# Ports.net
KiCad netlist of a schematic drawn in Altium Designer
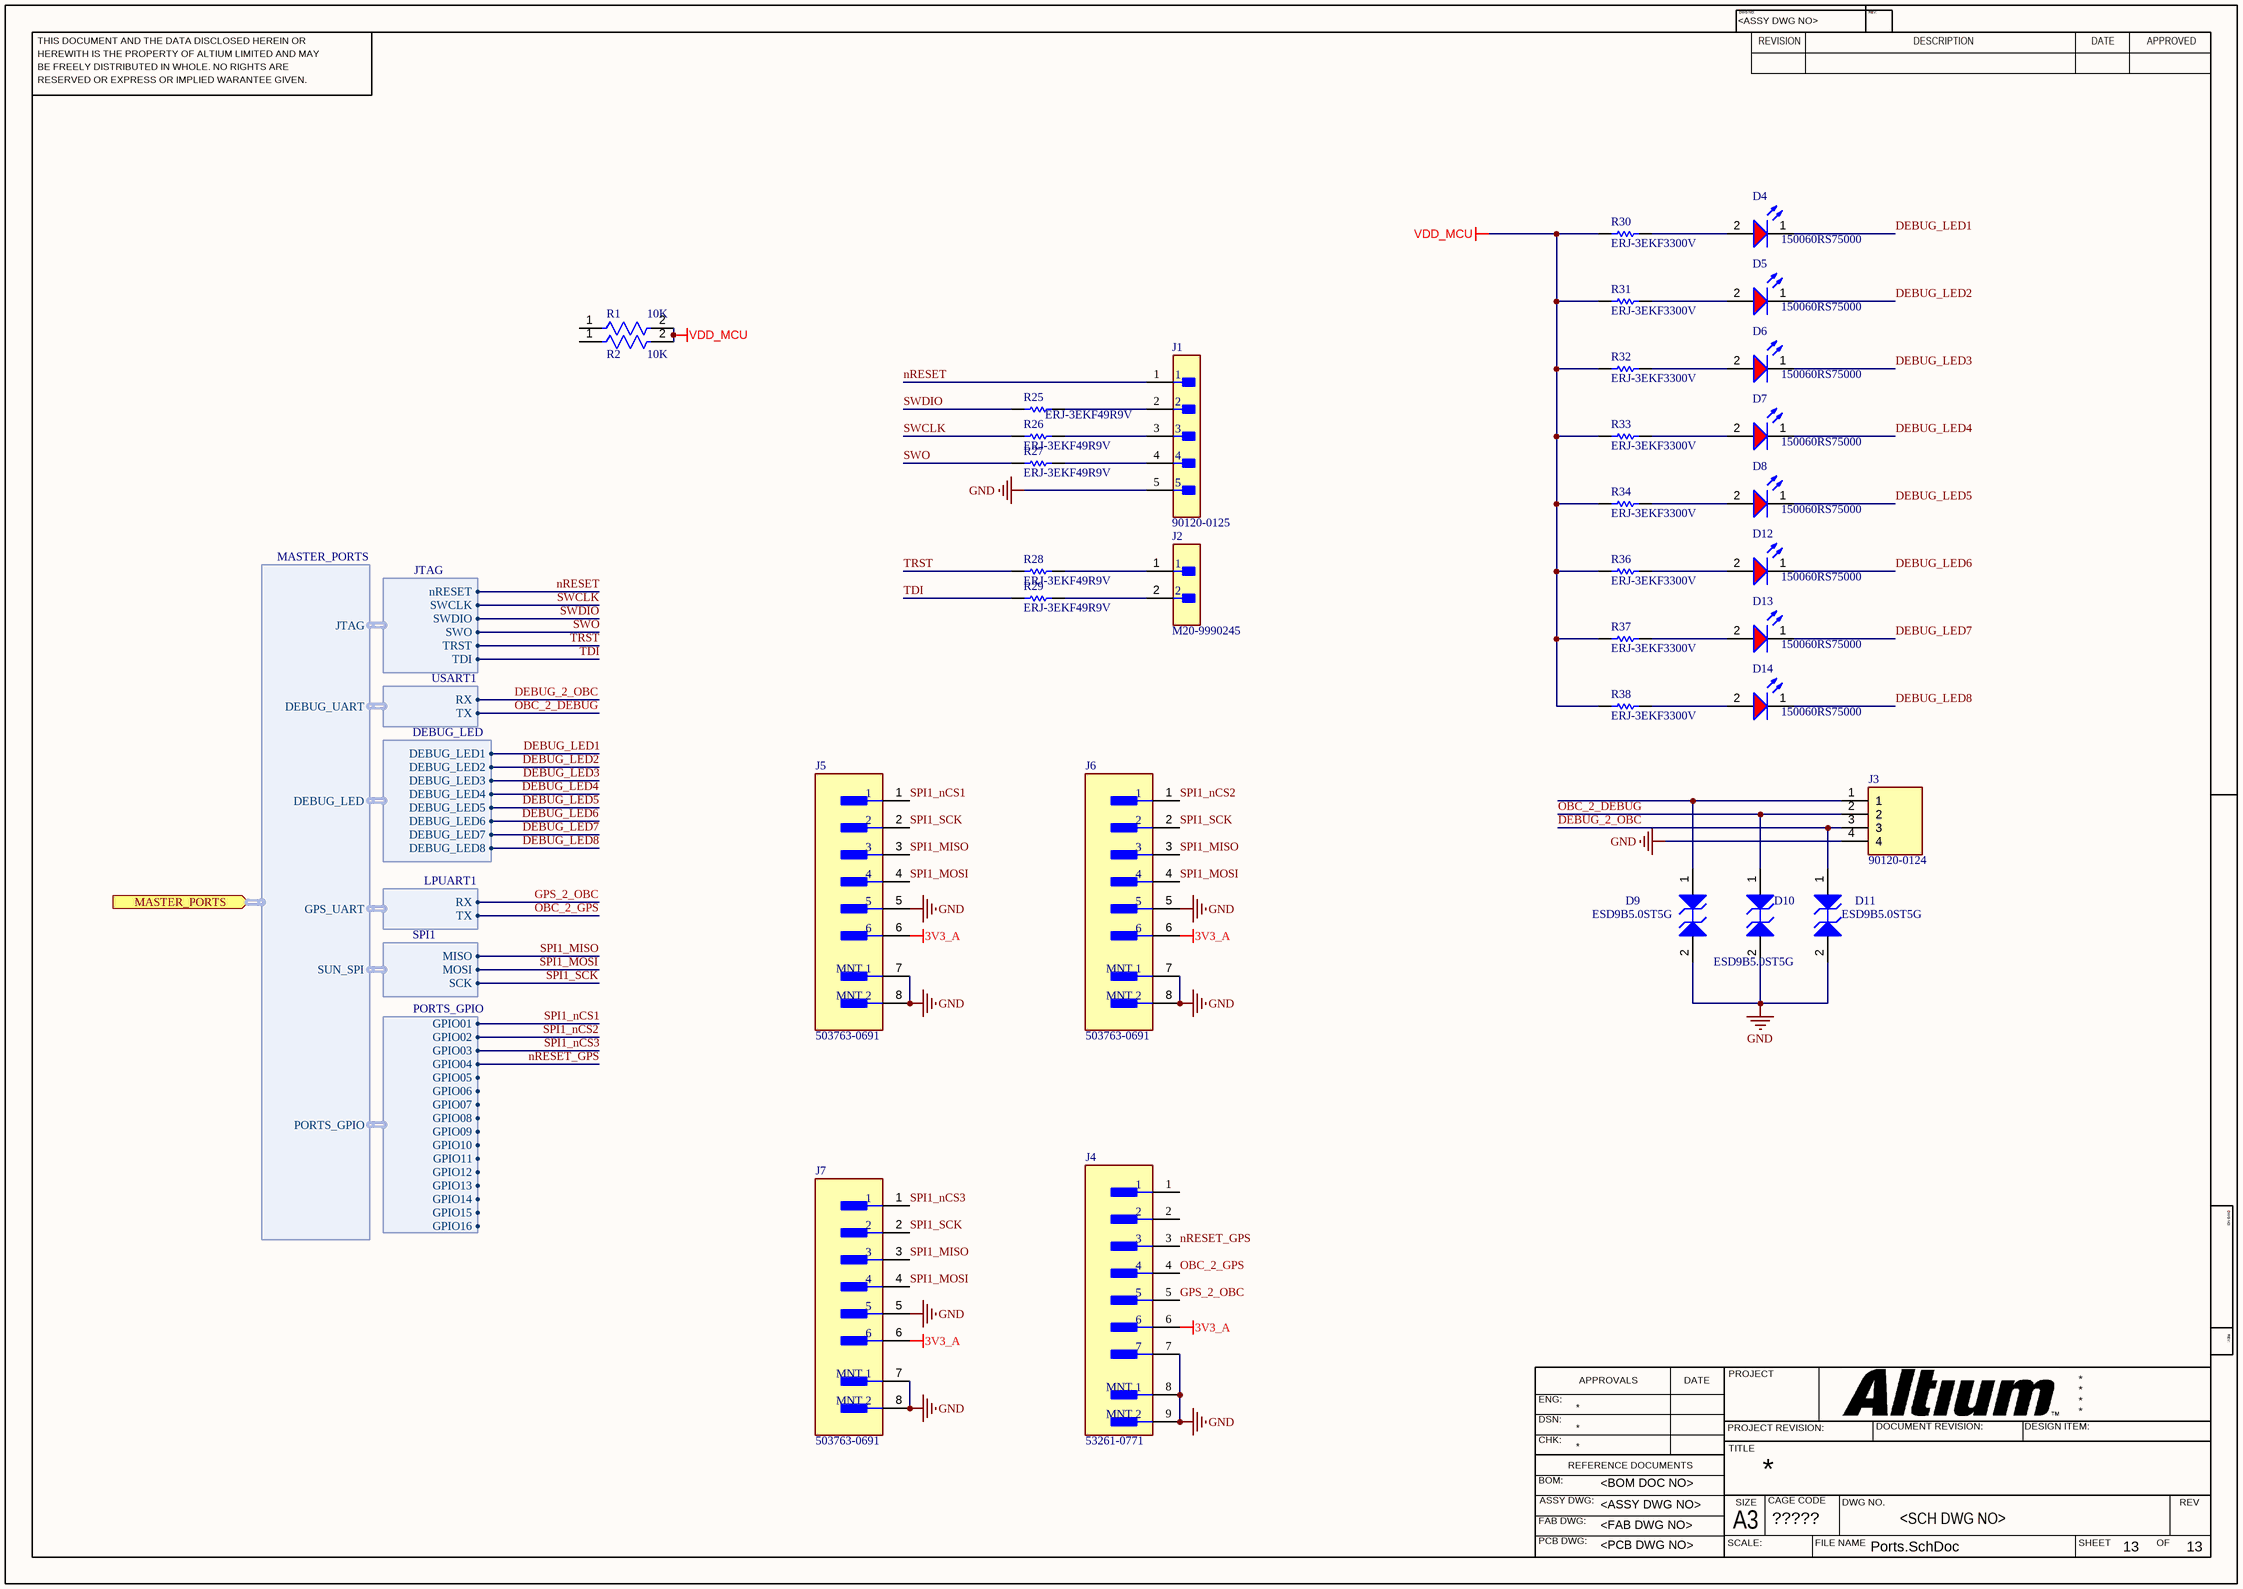
[diagram p0: Ports.SchDoc]

(export (version "E")
  (design (tool "Eeschema 10.0.6"))
  (components
    (comp (ref "D4")
      (value "150060RS75000")
      (footprint "WL-SMCW_0603_150060xx75000")
      (description "LED Low-Power Uni-Color Red 630nm 2V 2-Pin Chip 0603(1608Metric) T/R")
      (libsource (lib "Altium Content Vault") (part "LED_Red_2A-1K"))
    )
    (comp (ref "D5")
      (value "150060RS75000")
      (footprint "WL-SMCW_0603_150060xx75000")
      (description "LED Low-Power Uni-Color Red 630nm 2V 2-Pin Chip 0603(1608Metric) T/R")
      (libsource (lib "Altium Content Vault") (part "LED_Red_2A-1K"))
    )
    (comp (ref "D6")
      (value "150060RS75000")
      (footprint "WL-SMCW_0603_150060xx75000")
      (description "LED Low-Power Uni-Color Red 630nm 2V 2-Pin Chip 0603(1608Metric) T/R")
      (libsource (lib "Altium Content Vault") (part "LED_Red_2A-1K"))
    )
    (comp (ref "D7")
      (value "150060RS75000")
      (footprint "WL-SMCW_0603_150060xx75000")
      (description "LED Low-Power Uni-Color Red 630nm 2V 2-Pin Chip 0603(1608Metric) T/R")
      (libsource (lib "Altium Content Vault") (part "LED_Red_2A-1K"))
    )
    (comp (ref "D8")
      (value "150060RS75000")
      (footprint "WL-SMCW_0603_150060xx75000")
      (description "LED Low-Power Uni-Color Red 630nm 2V 2-Pin Chip 0603(1608Metric) T/R")
      (libsource (lib "Altium Content Vault") (part "LED_Red_2A-1K"))
    )
    (comp (ref "D9")
      (value "ESD9B5.0ST5G")
      (footprint "ONSC-SOD-923-2-514AB-01_V")
      (fields (field (name "MANUFACTURER") "On Semiconductor"))
      (libsource (lib "Altium Content Vault") (part "ONSC-A1A2-2"))
    )
    (comp (ref "D10")
      (value "ESD9B5.0ST5G")
      (footprint "ONSC-SOD-923-2-514AB-01_V")
      (fields (field (name "MANUFACTURER") "On Semiconductor"))
      (libsource (lib "Altium Content Vault") (part "ONSC-A1A2-2"))
    )
    (comp (ref "D11")
      (value "ESD9B5.0ST5G")
      (footprint "ONSC-SOD-923-2-514AB-01_V")
      (fields (field (name "MANUFACTURER") "On Semiconductor"))
      (libsource (lib "Altium Content Vault") (part "ONSC-A1A2-2"))
    )
    (comp (ref "D12")
      (value "150060RS75000")
      (footprint "WL-SMCW_0603_150060xx75000")
      (description "LED Low-Power Uni-Color Red 630nm 2V 2-Pin Chip 0603(1608Metric) T/R")
      (libsource (lib "Altium Content Vault") (part "LED_Red_2A-1K"))
    )
    (comp (ref "D13")
      (value "150060RS75000")
      (footprint "WL-SMCW_0603_150060xx75000")
      (description "LED Low-Power Uni-Color Red 630nm 2V 2-Pin Chip 0603(1608Metric) T/R")
      (libsource (lib "Altium Content Vault") (part "LED_Red_2A-1K"))
    )
    (comp (ref "D14")
      (value "150060RS75000")
      (footprint "WL-SMCW_0603_150060xx75000")
      (description "LED Low-Power Uni-Color Red 630nm 2V 2-Pin Chip 0603(1608Metric) T/R")
      (libsource (lib "Altium Content Vault") (part "LED_Red_2A-1K"))
    )
    (comp (ref "J1")
      (value "90120-0125")
      (footprint "FP-90120-0125-MFG")
      (description "90120-0125 2.54mm Pitch C-Grid III Header, Single Row, Vertical, 5 Circuits, Tin (Sn) Plating")
      (libsource (lib "Altium Content Vault") (part "bf93c07fd2649a848d0ec8585582aab"))
    )
    (comp (ref "J2")
      (value "M20-9990245")
      (footprint "FP-M20-9990245-MFG")
      (description "CONN HEADER VERT 2POS 2.54MM")
      (fields (field (name "VOLTAGE") "50V"))
      (libsource (lib "Altium Content Vault") (part "3bc925449376181038e59eaffc5286c"))
    )
    (comp (ref "J3")
      (value "90120-0124")
      (footprint "SamacSys:HDRV4W65P0X254_1X4_1016X254X945P")
      (description "Connector")
      (fields (field (name "MOUSER PART NUMBER") "538-90120-0124"))
      (libsource (lib "*") (part "90120-0124"))
    )
    (comp (ref "J4")
      (value "53261-0771")
      (footprint "FP-53261-0771-MFG")
      (description "CONN HEADER SMD R/A 7POS 1.25MM")
      (libsource (lib "Altium Content Vault") (part "bf8db8d8d9f0c3af2da8de9d3b974a9"))
    )
    (comp (ref "J5")
      (value "503763-0691")
      (footprint "FP-503763-0691-MFG")
      (description "CONN HEADER SMD R/A 6POS 1MM")
      (libsource (lib "Altium Content Vault") (part "ed24c53d9ba001d1a2a686240a95171"))
    )
    (comp (ref "J6")
      (value "503763-0691")
      (footprint "FP-503763-0691-MFG")
      (description "CONN HEADER SMD R/A 6POS 1MM")
      (libsource (lib "Altium Content Vault") (part "ed24c53d9ba001d1a2a686240a95171"))
    )
    (comp (ref "J7")
      (value "503763-0691")
      (footprint "FP-503763-0691-MFG")
      (description "CONN HEADER SMD R/A 6POS 1MM")
      (libsource (lib "Altium Content Vault") (part "ed24c53d9ba001d1a2a686240a95171"))
    )
    (comp (ref "R1")
      (value "10K")
      (footprint "FP-RK73B1J-MFG")
      (description "RES 10K OHM 5% 1/10W 0603")
      (fields (field (name "TOLERANCE") "5%"))
      (libsource (lib "Altium Content Vault") (part "1029c3af85768c4190bb7ad29bc67b5"))
    )
    (comp (ref "R2")
      (value "10K")
      (footprint "FP-RK73B1J-MFG")
      (description "RES 10K OHM 5% 1/10W 0603")
      (fields (field (name "TOLERANCE") "5%"))
      (libsource (lib "Altium Content Vault") (part "1029c3af85768c4190bb7ad29bc67b5"))
    )
    (comp (ref "R25")
      (value "ERJ-3EKF49R9V")
      (footprint "RESC1608X55X30ML15T15")
      (fields (field (name "MANUFACTURER") "Panasonic"))
      (libsource (lib "Altium Content Vault") (part "RES"))
    )
    (comp (ref "R26")
      (value "ERJ-3EKF49R9V")
      (footprint "RESC1608X55X30ML15T15")
      (fields (field (name "MANUFACTURER") "Panasonic"))
      (libsource (lib "Altium Content Vault") (part "RES"))
    )
    (comp (ref "R27")
      (value "ERJ-3EKF49R9V")
      (footprint "RESC1608X55X30ML15T15")
      (fields (field (name "MANUFACTURER") "Panasonic"))
      (libsource (lib "Altium Content Vault") (part "RES"))
    )
    (comp (ref "R28")
      (value "ERJ-3EKF49R9V")
      (footprint "RESC1608X55X30ML15T15")
      (fields (field (name "MANUFACTURER") "Panasonic"))
      (libsource (lib "Altium Content Vault") (part "RES"))
    )
    (comp (ref "R29")
      (value "ERJ-3EKF49R9V")
      (footprint "RESC1608X55X30ML15T15")
      (fields (field (name "MANUFACTURER") "Panasonic"))
      (libsource (lib "Altium Content Vault") (part "RES"))
    )
    (comp (ref "R30")
      (value "ERJ-3EKF3300V")
      (footprint "RESC1608X55X30LL15T15")
      (description "Chip Resistor, 330 Ohm, +/- 1%, 0.1 W, -55 to 155 degC, 0603 (1608 Metric), RoHS, Tape and Reel")
      (libsource (lib "Altium Content Vault") (part "RES-2"))
    )
    (comp (ref "R31")
      (value "ERJ-3EKF3300V")
      (footprint "RESC1608X55X30LL15T15")
      (description "Chip Resistor, 330 Ohm, +/- 1%, 0.1 W, -55 to 155 degC, 0603 (1608 Metric), RoHS, Tape and Reel")
      (libsource (lib "Altium Content Vault") (part "RES-2"))
    )
    (comp (ref "R32")
      (value "ERJ-3EKF3300V")
      (footprint "RESC1608X55X30LL15T15")
      (description "Chip Resistor, 330 Ohm, +/- 1%, 0.1 W, -55 to 155 degC, 0603 (1608 Metric), RoHS, Tape and Reel")
      (libsource (lib "Altium Content Vault") (part "RES-2"))
    )
    (comp (ref "R33")
      (value "ERJ-3EKF3300V")
      (footprint "RESC1608X55X30LL15T15")
      (description "Chip Resistor, 330 Ohm, +/- 1%, 0.1 W, -55 to 155 degC, 0603 (1608 Metric), RoHS, Tape and Reel")
      (libsource (lib "Altium Content Vault") (part "RES-2"))
    )
    (comp (ref "R34")
      (value "ERJ-3EKF3300V")
      (footprint "RESC1608X55X30LL15T15")
      (description "Chip Resistor, 330 Ohm, +/- 1%, 0.1 W, -55 to 155 degC, 0603 (1608 Metric), RoHS, Tape and Reel")
      (libsource (lib "Altium Content Vault") (part "RES-2"))
    )
    (comp (ref "R36")
      (value "ERJ-3EKF3300V")
      (footprint "RESC1608X55X30LL15T15")
      (description "Chip Resistor, 330 Ohm, +/- 1%, 0.1 W, -55 to 155 degC, 0603 (1608 Metric), RoHS, Tape and Reel")
      (libsource (lib "Altium Content Vault") (part "RES-2"))
    )
    (comp (ref "R37")
      (value "ERJ-3EKF3300V")
      (footprint "RESC1608X55X30LL15T15")
      (description "Chip Resistor, 330 Ohm, +/- 1%, 0.1 W, -55 to 155 degC, 0603 (1608 Metric), RoHS, Tape and Reel")
      (libsource (lib "Altium Content Vault") (part "RES-2"))
    )
    (comp (ref "R38")
      (value "ERJ-3EKF3300V")
      (footprint "RESC1608X55X30LL15T15")
      (description "Chip Resistor, 330 Ohm, +/- 1%, 0.1 W, -55 to 155 degC, 0603 (1608 Metric), RoHS, Tape and Reel")
      (libsource (lib "Altium Content Vault") (part "RES-2"))
    )
  )
  (nets
    (net (code "8") (name "/DEBUG_2_OBC") (class "Default")
      (node (ref "D11") (pin "1") (pinfunction "A1_1") (pintype "passive"))
      (node (ref "J3") (pin "3") (pinfunction "3_3") (pintype "passive"))
    )
    (net (code "9") (name "/DEBUG_LED1") (class "Default")
      (node (ref "D4") (pin "1") (pinfunction "K_1") (pintype "passive"))
    )
    (net (code "10") (name "/DEBUG_LED2") (class "Default")
      (node (ref "D5") (pin "1") (pinfunction "K_1") (pintype "passive"))
    )
    (net (code "11") (name "/DEBUG_LED3") (class "Default")
      (node (ref "D6") (pin "1") (pinfunction "K_1") (pintype "passive"))
    )
    (net (code "12") (name "/DEBUG_LED4") (class "Default")
      (node (ref "D7") (pin "1") (pinfunction "K_1") (pintype "passive"))
    )
    (net (code "13") (name "/DEBUG_LED5") (class "Default")
      (node (ref "D8") (pin "1") (pinfunction "K_1") (pintype "passive"))
    )
    (net (code "14") (name "/DEBUG_LED6") (class "Default")
      (node (ref "D12") (pin "1") (pinfunction "K_1") (pintype "passive"))
    )
    (net (code "15") (name "/DEBUG_LED7") (class "Default")
      (node (ref "D13") (pin "1") (pinfunction "K_1") (pintype "passive"))
    )
    (net (code "16") (name "/DEBUG_LED8") (class "Default")
      (node (ref "D14") (pin "1") (pinfunction "K_1") (pintype "passive"))
    )
    (net (code "17") (name "/GPS_2_OBC") (class "Default")
      (node (ref "J4") (pin "5") (pinfunction "5_5") (pintype "passive"))
    )
    (net (code "19") (name "/OBC_2_DEBUG") (class "Default")
      (node (ref "D10") (pin "1") (pinfunction "A1_1") (pintype "passive"))
      (node (ref "J3") (pin "2") (pinfunction "2_2") (pintype "passive"))
    )
    (net (code "20") (name "/OBC_2_GPS") (class "Default")
      (node (ref "J4") (pin "4") (pinfunction "4_4") (pintype "passive"))
    )
    (net (code "21") (name "/SPI1_MISO") (class "Default")
      (node (ref "J5") (pin "3") (pinfunction "3_3") (pintype "passive"))
      (node (ref "J6") (pin "3") (pinfunction "3_3") (pintype "passive"))
      (node (ref "J7") (pin "3") (pinfunction "3_3") (pintype "passive"))
    )
    (net (code "22") (name "/SPI1_MOSI") (class "Default")
      (node (ref "J5") (pin "4") (pinfunction "4_4") (pintype "passive"))
      (node (ref "J6") (pin "4") (pinfunction "4_4") (pintype "passive"))
      (node (ref "J7") (pin "4") (pinfunction "4_4") (pintype "passive"))
    )
    (net (code "23") (name "/SPI1_SCK") (class "Default")
      (node (ref "J5") (pin "2") (pinfunction "2_2") (pintype "passive"))
      (node (ref "J6") (pin "2") (pinfunction "2_2") (pintype "passive"))
      (node (ref "J7") (pin "2") (pinfunction "2_2") (pintype "passive"))
    )
    (net (code "24") (name "/SPI1_nCS1") (class "Default")
      (node (ref "J5") (pin "1") (pinfunction "1_1") (pintype "passive"))
    )
    (net (code "25") (name "/SPI1_nCS2") (class "Default")
      (node (ref "J6") (pin "1") (pinfunction "1_1") (pintype "passive"))
    )
    (net (code "26") (name "/SPI1_nCS3") (class "Default")
      (node (ref "J7") (pin "1") (pinfunction "1_1") (pintype "passive"))
    )
    (net (code "27") (name "/SWCLK") (class "Default")
      (node (ref "R26") (pin "1") (pinfunction "1_1") (pintype "passive"))
    )
    (net (code "28") (name "/SWDIO") (class "Default")
      (node (ref "R25") (pin "1") (pinfunction "1_1") (pintype "passive"))
    )
    (net (code "29") (name "/SWO") (class "Default")
      (node (ref "R27") (pin "1") (pinfunction "1_1") (pintype "passive"))
    )
    (net (code "30") (name "/TDI") (class "Default")
      (node (ref "R29") (pin "1") (pinfunction "1_1") (pintype "passive"))
    )
    (net (code "31") (name "/TRST") (class "Default")
      (node (ref "R28") (pin "1") (pinfunction "1_1") (pintype "passive"))
    )
    (net (code "32") (name "/nRESET") (class "Default")
      (node (ref "J1") (pin "1") (pinfunction "1_1") (pintype "passive"))
    )
    (net (code "33") (name "/nRESET_GPS") (class "Default")
      (node (ref "J4") (pin "3") (pinfunction "3_3") (pintype "passive"))
    )
    (net (code "40") (name "3V3_A") (class "Default")
      (node (ref "J4") (pin "6") (pinfunction "6_6") (pintype "passive"))
      (node (ref "J5") (pin "6") (pinfunction "6_6") (pintype "passive"))
      (node (ref "J6") (pin "6") (pinfunction "6_6") (pintype "passive"))
      (node (ref "J7") (pin "6") (pinfunction "6_6") (pintype "passive"))
    )
    (net (code "41") (name "GND") (class "Default")
      (node (ref "D10") (pin "2") (pinfunction "A2_2") (pintype "passive"))
      (node (ref "D11") (pin "2") (pinfunction "A2_2") (pintype "passive"))
      (node (ref "D9") (pin "2") (pinfunction "A2_2") (pintype "passive"))
      (node (ref "J1") (pin "5") (pinfunction "5_5") (pintype "passive"))
      (node (ref "J3") (pin "4") (pinfunction "4_4") (pintype "passive"))
      (node (ref "J4") (pin "7") (pinfunction "7_7") (pintype "passive"))
      (node (ref "J4") (pin "8") (pinfunction "MNT_1_8") (pintype "passive"))
      (node (ref "J4") (pin "9") (pinfunction "MNT_2_9") (pintype "passive"))
      (node (ref "J5") (pin "5") (pinfunction "5_5") (pintype "passive"))
      (node (ref "J5") (pin "7") (pinfunction "MNT_1_7") (pintype "passive"))
      (node (ref "J5") (pin "8") (pinfunction "MNT_2_8") (pintype "passive"))
      (node (ref "J6") (pin "5") (pinfunction "5_5") (pintype "passive"))
      (node (ref "J6") (pin "7") (pinfunction "MNT_1_7") (pintype "passive"))
      (node (ref "J6") (pin "8") (pinfunction "MNT_2_8") (pintype "passive"))
      (node (ref "J7") (pin "5") (pinfunction "5_5") (pintype "passive"))
      (node (ref "J7") (pin "7") (pinfunction "MNT_1_7") (pintype "passive"))
      (node (ref "J7") (pin "8") (pinfunction "MNT_2_8") (pintype "passive"))
    )
    (net (code "42") (name "Net-(D4-A)") (class "Default")
      (node (ref "D4") (pin "2") (pinfunction "A_2") (pintype "passive"))
      (node (ref "R30") (pin "2") (pinfunction "2_2") (pintype "passive"))
    )
    (net (code "43") (name "Net-(D5-A)") (class "Default")
      (node (ref "D5") (pin "2") (pinfunction "A_2") (pintype "passive"))
      (node (ref "R31") (pin "2") (pinfunction "2_2") (pintype "passive"))
    )
    (net (code "44") (name "Net-(D6-A)") (class "Default")
      (node (ref "D6") (pin "2") (pinfunction "A_2") (pintype "passive"))
      (node (ref "R32") (pin "2") (pinfunction "2_2") (pintype "passive"))
    )
    (net (code "45") (name "Net-(D7-A)") (class "Default")
      (node (ref "D7") (pin "2") (pinfunction "A_2") (pintype "passive"))
      (node (ref "R33") (pin "2") (pinfunction "2_2") (pintype "passive"))
    )
    (net (code "46") (name "Net-(D8-A)") (class "Default")
      (node (ref "D8") (pin "2") (pinfunction "A_2") (pintype "passive"))
      (node (ref "R34") (pin "2") (pinfunction "2_2") (pintype "passive"))
    )
    (net (code "47") (name "Net-(D9-A1)") (class "Default")
      (node (ref "D9") (pin "1") (pinfunction "A1_1") (pintype "passive"))
      (node (ref "J3") (pin "1") (pinfunction "1_1") (pintype "passive"))
    )
    (net (code "48") (name "Net-(D12-A)") (class "Default")
      (node (ref "D12") (pin "2") (pinfunction "A_2") (pintype "passive"))
      (node (ref "R36") (pin "2") (pinfunction "2_2") (pintype "passive"))
    )
    (net (code "49") (name "Net-(D13-A)") (class "Default")
      (node (ref "D13") (pin "2") (pinfunction "A_2") (pintype "passive"))
      (node (ref "R37") (pin "2") (pinfunction "2_2") (pintype "passive"))
    )
    (net (code "50") (name "Net-(D14-A)") (class "Default")
      (node (ref "D14") (pin "2") (pinfunction "A_2") (pintype "passive"))
      (node (ref "R38") (pin "2") (pinfunction "2_2") (pintype "passive"))
    )
    (net (code "51") (name "Net-(J1-Pad2)") (class "Default")
      (node (ref "J1") (pin "2") (pinfunction "2_2") (pintype "passive"))
      (node (ref "R25") (pin "2") (pinfunction "2_2") (pintype "passive"))
    )
    (net (code "52") (name "Net-(J1-Pad3)") (class "Default")
      (node (ref "J1") (pin "3") (pinfunction "3_3") (pintype "passive"))
      (node (ref "R26") (pin "2") (pinfunction "2_2") (pintype "passive"))
    )
    (net (code "53") (name "Net-(J1-Pad4)") (class "Default")
      (node (ref "J1") (pin "4") (pinfunction "4_4") (pintype "passive"))
      (node (ref "R27") (pin "2") (pinfunction "2_2") (pintype "passive"))
    )
    (net (code "54") (name "Net-(J2-Pad1)") (class "Default")
      (node (ref "J2") (pin "1") (pinfunction "1_1") (pintype "passive"))
      (node (ref "R28") (pin "2") (pinfunction "2_2") (pintype "passive"))
    )
    (net (code "55") (name "Net-(J2-Pad2)") (class "Default")
      (node (ref "J2") (pin "2") (pinfunction "2_2") (pintype "passive"))
      (node (ref "R29") (pin "2") (pinfunction "2_2") (pintype "passive"))
    )
    (net (code "56") (name "VDD_MCU") (class "Default")
      (node (ref "R1") (pin "2") (pinfunction "2_2") (pintype "passive"))
      (node (ref "R2") (pin "2") (pinfunction "2_2") (pintype "passive"))
      (node (ref "R30") (pin "1") (pinfunction "1_1") (pintype "passive"))
      (node (ref "R31") (pin "1") (pinfunction "1_1") (pintype "passive"))
      (node (ref "R32") (pin "1") (pinfunction "1_1") (pintype "passive"))
      (node (ref "R33") (pin "1") (pinfunction "1_1") (pintype "passive"))
      (node (ref "R34") (pin "1") (pinfunction "1_1") (pintype "passive"))
      (node (ref "R36") (pin "1") (pinfunction "1_1") (pintype "passive"))
      (node (ref "R37") (pin "1") (pinfunction "1_1") (pintype "passive"))
      (node (ref "R38") (pin "1") (pinfunction "1_1") (pintype "passive"))
    )
    (net (code "57") (name "unconnected-(J4-Pad1)") (class "Default")
      (node (ref "J4") (pin "1") (pinfunction "1_1") (pintype "passive"))
    )
    (net (code "58") (name "unconnected-(J4-Pad2)") (class "Default")
      (node (ref "J4") (pin "2") (pinfunction "2_2") (pintype "passive"))
    )
    (net (code "59") (name "unconnected-(R1-Pad1)") (class "Default")
      (node (ref "R1") (pin "1") (pinfunction "1_1") (pintype "passive"))
    )
    (net (code "60") (name "unconnected-(R2-Pad1)") (class "Default")
      (node (ref "R2") (pin "1") (pinfunction "1_1") (pintype "passive"))
    )
  )
)
